# RS485_ISO.net
KiCad netlist of a schematic drawn in Altium Designer
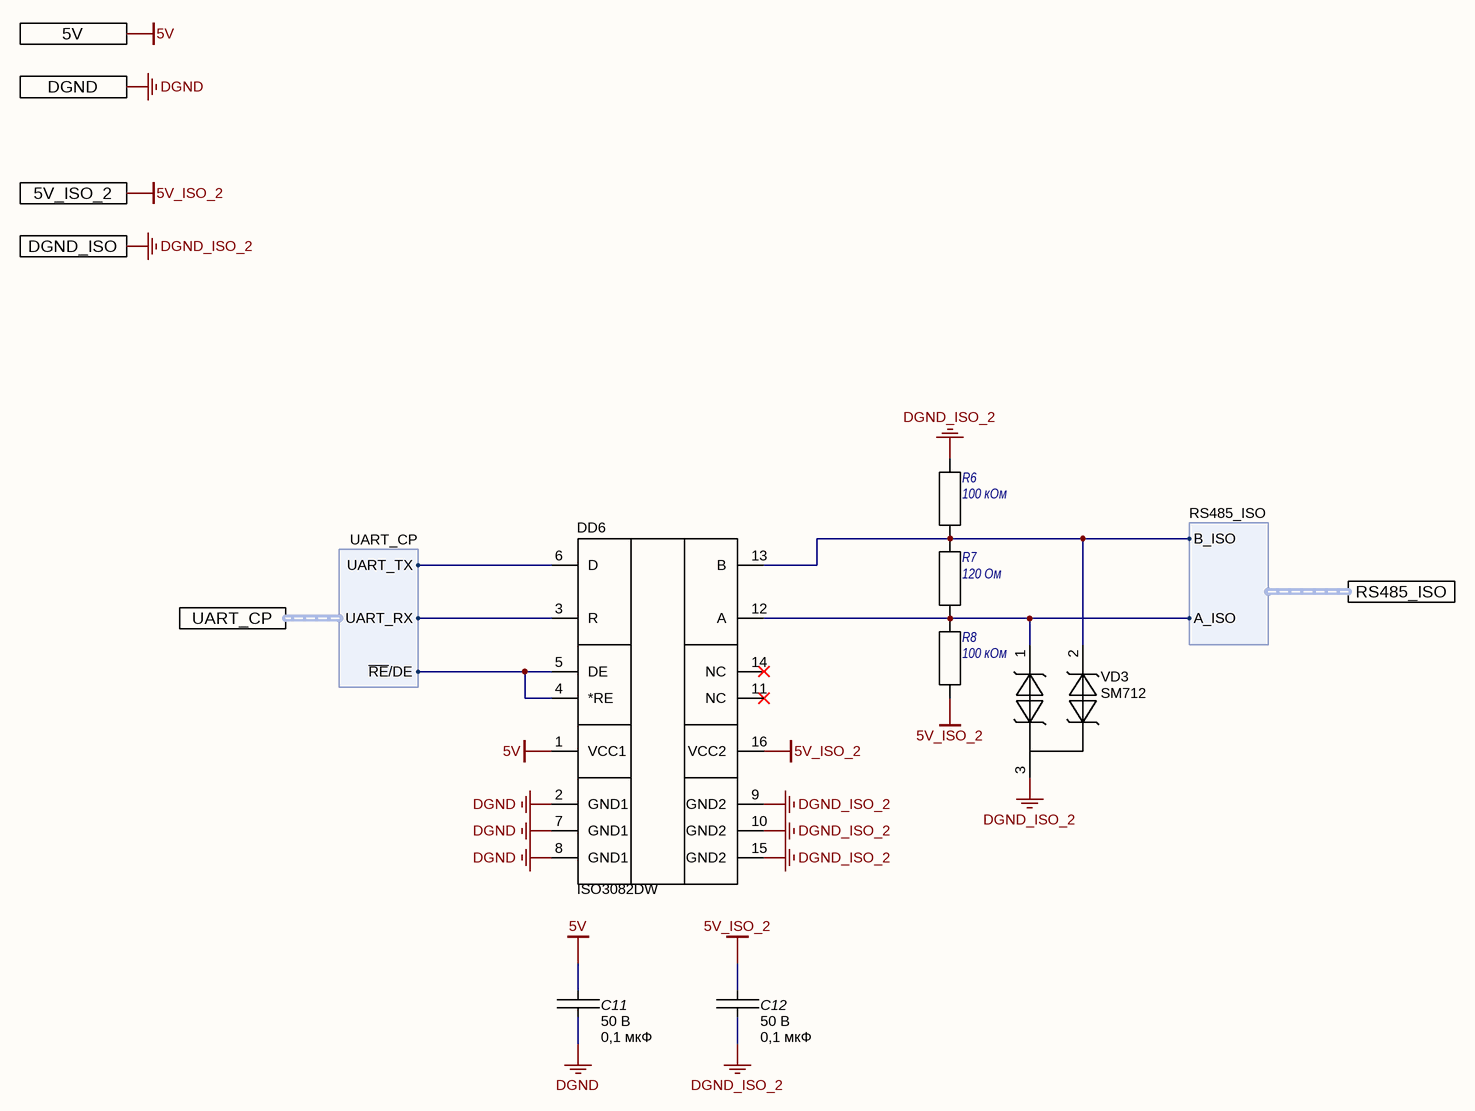
[diagram p0: RS485_ISO.SchDoc]

(export (version "E")
  (design (tool "Eeschema 10.0.6"))
  (components
    (comp (ref "C11")
      (value "0,1 мкФ")
      (footprint "C0603C")
      (description "SMD 0603 ; X7R; 0,1 мкФ; 50 В")
      (fields
        (field (name "PART NUMBER") "CC0603KRX7R9BB104")
        (field (name "MANUFACTURER") "YAGEO")
        (field (name "VOLTAGE") "50 В")
      )
      (libsource (lib "Capacitors") (part "CC0603KRX7R9BB104"))
    )
    (comp (ref "C12")
      (value "0,1 мкФ")
      (footprint "C0603C")
      (description "SMD 0603 ; X7R; 0,1 мкФ; 50 В")
      (fields
        (field (name "PART NUMBER") "CC0603KRX7R9BB104")
        (field (name "MANUFACTURER") "YAGEO")
        (field (name "VOLTAGE") "50 В")
      )
      (libsource (lib "Capacitors") (part "CC0603KRX7R9BB104"))
    )
    (comp (ref "DD6")
      (value "ISO3082DW")
      (footprint "SOIC-Wide-16")
      (description "RS-485 Transceivers")
      (fields (field (name "MANUFACTURER") "Texas Instruments"))
      (libsource (lib "IC") (part "ISO3082DW"))
    )
    (comp (ref "R6")
      (value "100 кОм")
      (footprint "C0603R")
      (description "SMD 0603; 0,1; 1%; 100 кОм")
      (fields (field (name "PART NUMBER") "RC0603FR-07100KL") (field (name "POWER") "0,1"))
      (libsource (lib "Resistors") (part "RC0603FR-07100KL"))
    )
    (comp (ref "R7")
      (value "120 Ом")
      (footprint "C0603R")
      (description "SMD 0603; 0,1; 1%; 120 Ом")
      (fields (field (name "PART NUMBER") "RC0603FR-07120RL") (field (name "POWER") "0,1"))
      (libsource (lib "Resistors") (part "RC0603FR-07120RL"))
    )
    (comp (ref "R8")
      (value "100 кОм")
      (footprint "C0603R")
      (description "SMD 0603; 0,1; 1%; 100 кОм")
      (fields (field (name "PART NUMBER") "RC0603FR-07100KL") (field (name "POWER") "0,1"))
      (libsource (lib "Resistors") (part "RC0603FR-07100KL"))
    )
    (comp (ref "VD3")
      (value "SM712")
      (footprint "SOT23-3")
      (description "TVS RS485")
      (fields (field (name "MANUFACTURER") "Semtech") (field (name "PART NUMBER") "SM712.TCT"))
      (libsource (lib "VD") (part "SM712.TCT"))
    )
  )
  (nets
    (net (code "3") (name "/A_ISO") (class "Default")
      (node (ref "DD6") (pin "12") (pinfunction "A_12") (pintype "passive"))
      (node (ref "R7") (pin "2") (pinfunction "2_2") (pintype "passive"))
      (node (ref "R8") (pin "1") (pinfunction "1_1") (pintype "passive"))
      (node (ref "VD3") (pin "1") (pinfunction "1_1") (pintype "passive"))
    )
    (net (code "4") (name "/B_ISO") (class "Default")
      (node (ref "DD6") (pin "13") (pinfunction "B_13") (pintype "passive"))
      (node (ref "R6") (pin "2") (pinfunction "2_2") (pintype "passive"))
      (node (ref "R7") (pin "1") (pinfunction "1_1") (pintype "passive"))
      (node (ref "VD3") (pin "2") (pinfunction "2_2") (pintype "passive"))
    )
    (net (code "5") (name "/UART_RX") (class "Default")
      (node (ref "DD6") (pin "3") (pinfunction "R_3") (pintype "passive"))
    )
    (net (code "6") (name "/UART_TX") (class "Default")
      (node (ref "DD6") (pin "6") (pinfunction "D_6") (pintype "passive"))
    )
    (net (code "9") (name "/~{RE}{slash}DE") (class "Default")
      (node (ref "DD6") (pin "4") (pinfunction "*RE_4") (pintype "passive"))
      (node (ref "DD6") (pin "5") (pinfunction "DE_5") (pintype "passive"))
    )
    (net (code "10") (name "5V") (class "Default")
      (node (ref "C11") (pin "1") (pinfunction "1_1") (pintype "passive"))
      (node (ref "DD6") (pin "1") (pinfunction "VCC1_1") (pintype "power_in"))
    )
    (net (code "11") (name "5V_ISO_2") (class "Default")
      (node (ref "C12") (pin "1") (pinfunction "1_1") (pintype "passive"))
      (node (ref "DD6") (pin "16") (pinfunction "VCC2_16") (pintype "power_in"))
      (node (ref "R8") (pin "2") (pinfunction "2_2") (pintype "passive"))
    )
    (net (code "12") (name "DGND") (class "Default")
      (node (ref "C11") (pin "2") (pinfunction "2_2") (pintype "passive"))
      (node (ref "DD6") (pin "2") (pinfunction "GND1_2") (pintype "power_in"))
      (node (ref "DD6") (pin "7") (pinfunction "GND1_7") (pintype "power_in"))
      (node (ref "DD6") (pin "8") (pinfunction "GND1_8") (pintype "power_in"))
    )
    (net (code "13") (name "DGND_ISO_2") (class "Default")
      (node (ref "C12") (pin "2") (pinfunction "2_2") (pintype "passive"))
      (node (ref "DD6") (pin "10") (pinfunction "GND2_10") (pintype "power_in"))
      (node (ref "DD6") (pin "15") (pinfunction "GND2_15") (pintype "power_in"))
      (node (ref "DD6") (pin "9") (pinfunction "GND2_9") (pintype "power_in"))
      (node (ref "R6") (pin "1") (pinfunction "1_1") (pintype "passive"))
      (node (ref "VD3") (pin "3") (pinfunction "3_3") (pintype "passive"))
    )
    (net (code "14") (name "unconnected-(DD6-NC-Pad11)") (class "Default")
      (node (ref "DD6") (pin "11") (pinfunction "NC_11") (pintype "passive+no_connect"))
    )
    (net (code "15") (name "unconnected-(DD6-NC-Pad14)") (class "Default")
      (node (ref "DD6") (pin "14") (pinfunction "NC_14") (pintype "passive+no_connect"))
    )
  )
)
